# nucleo-shield.net
KiCad netlist of a schematic drawn in EAGLE
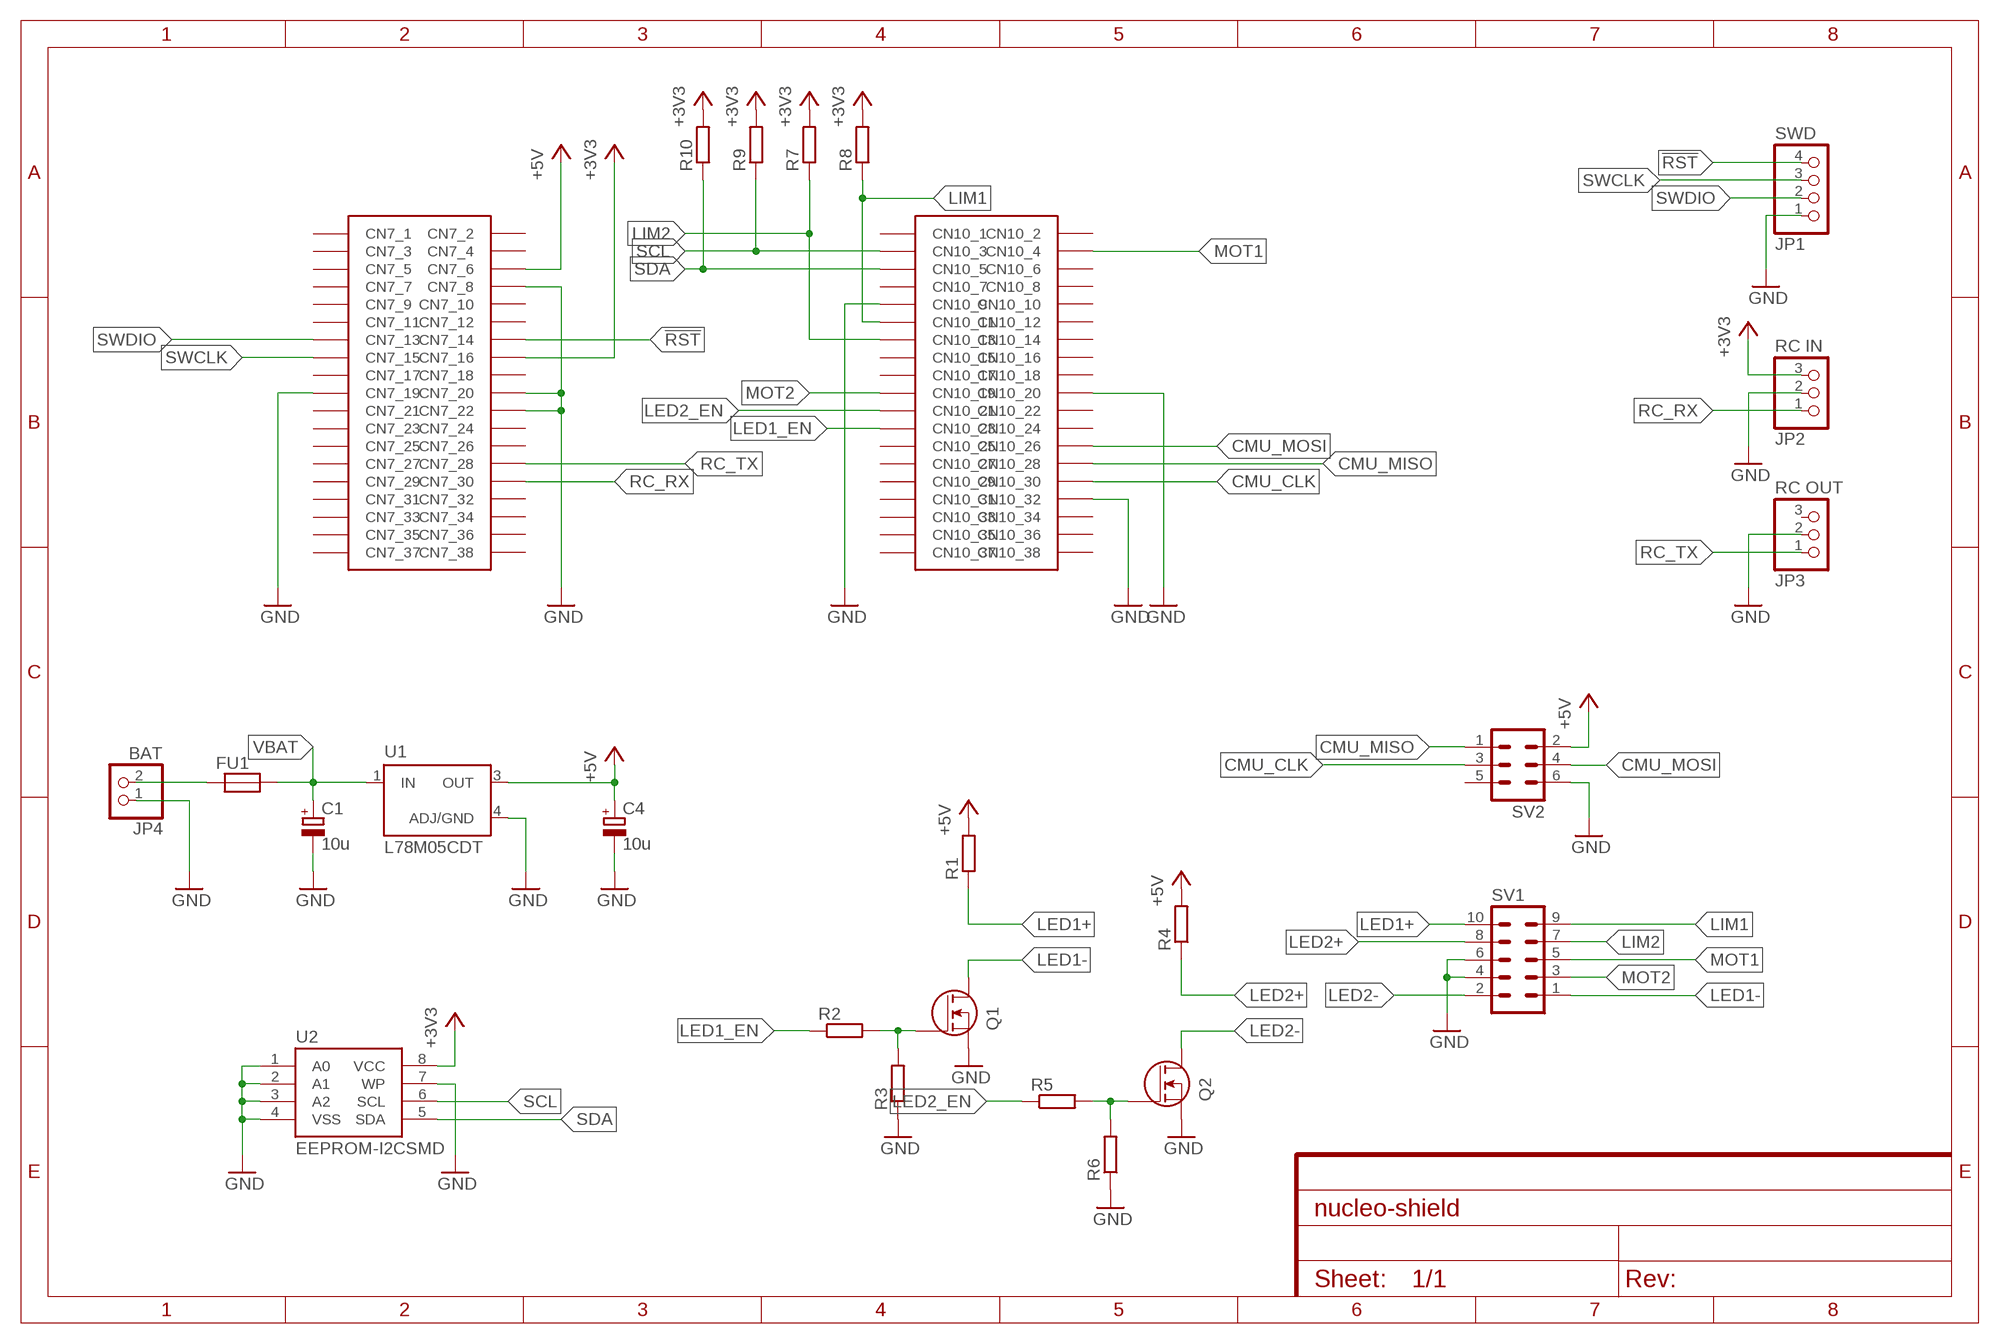
[diagram p0: schematic, sheet 1]

(export (version "E")
  (design (tool "Eeschema 10.0.6"))
  (components
    (comp (ref "C1")
      (value "10u")
      (footprint "eagle-import:SMC_A")
      (libsource (lib "eagle-import") (part "CPOL-EUSMCA"))
    )
    (comp (ref "C4")
      (value "10u")
      (footprint "eagle-import:SMC_A")
      (libsource (lib "eagle-import") (part "CPOL-EUSMCA"))
    )
    (comp (ref "FU1")
      (value "PTC_FUSE")
      (footprint "eagle-import:C1812K")
      (libsource (lib "eagle-import") (part "PTC_FUSE"))
    )
    (comp (ref "JP1")
      (value "SWD")
      (footprint "eagle-import:1X04")
      (libsource (lib "eagle-import") (part "PINHD-1X4"))
    )
    (comp (ref "JP2")
      (value "RC IN")
      (footprint "eagle-import:1X03")
      (libsource (lib "eagle-import") (part "PINHD-1X3"))
    )
    (comp (ref "JP3")
      (value "RC OUT")
      (footprint "eagle-import:1X03")
      (libsource (lib "eagle-import") (part "PINHD-1X3"))
    )
    (comp (ref "JP4")
      (value "BAT")
      (footprint "eagle-import:1X02")
      (libsource (lib "eagle-import") (part "PINHD-1X2"))
    )
    (comp (ref "Q1")
      (value "MOSFET-N-SOT23-3")
      (footprint "eagle-import:SOT23-3")
      (libsource (lib "eagle-import") (part "MOSFET-N-SOT23-3"))
    )
    (comp (ref "Q2")
      (value "MOSFET-N-SOT23-3")
      (footprint "eagle-import:SOT23-3")
      (libsource (lib "eagle-import") (part "MOSFET-N-SOT23-3"))
    )
    (comp (ref "R1")
      (value "R-EU_R0805")
      (footprint "eagle-import:R0805")
      (libsource (lib "eagle-import") (part "R-EU_R0805"))
    )
    (comp (ref "R2")
      (value "R-EU_R0805")
      (footprint "eagle-import:R0805")
      (libsource (lib "eagle-import") (part "R-EU_R0805"))
    )
    (comp (ref "R3")
      (value "R-EU_R0805")
      (footprint "eagle-import:R0805")
      (libsource (lib "eagle-import") (part "R-EU_R0805"))
    )
    (comp (ref "R4")
      (value "R-EU_R0805")
      (footprint "eagle-import:R0805")
      (libsource (lib "eagle-import") (part "R-EU_R0805"))
    )
    (comp (ref "R5")
      (value "R-EU_R0805")
      (footprint "eagle-import:R0805")
      (libsource (lib "eagle-import") (part "R-EU_R0805"))
    )
    (comp (ref "R6")
      (value "R-EU_R0805")
      (footprint "eagle-import:R0805")
      (libsource (lib "eagle-import") (part "R-EU_R0805"))
    )
    (comp (ref "R7")
      (value "R-EU_R0805")
      (footprint "eagle-import:R0805")
      (libsource (lib "eagle-import") (part "R-EU_R0805"))
    )
    (comp (ref "R8")
      (value "R-EU_R0805")
      (footprint "eagle-import:R0805")
      (libsource (lib "eagle-import") (part "R-EU_R0805"))
    )
    (comp (ref "R9")
      (value "R-EU_R0805")
      (footprint "eagle-import:R0805")
      (libsource (lib "eagle-import") (part "R-EU_R0805"))
    )
    (comp (ref "R10")
      (value "R-EU_R0805")
      (footprint "eagle-import:R0805")
      (libsource (lib "eagle-import") (part "R-EU_R0805"))
    )
    (comp (ref "SV1")
      (value "ML10L")
      (footprint "eagle-import:ML10L")
      (libsource (lib "eagle-import") (part "ML10L"))
    )
    (comp (ref "SV2")
      (value "ML6L")
      (footprint "eagle-import:ML6L")
      (libsource (lib "eagle-import") (part "ML6L"))
    )
    (comp (ref "U$2")
      (value "NUCLEO-MORPHO-64")
      (footprint "eagle-import:NUCLEO-64-MORPHO")
      (libsource (lib "eagle-import") (part "NUCLEO-MORPHO-64"))
    )
    (comp (ref "U1")
      (value "L78M05CDT")
      (footprint "eagle-import:DPAK")
      (libsource (lib "eagle-import") (part "VREG-3PIN-DPAK"))
    )
    (comp (ref "U2")
      (value "EEPROM-I2CSMD")
      (footprint "eagle-import:SO08")
      (libsource (lib "eagle-import") (part "EEPROM-I2CSMD"))
    )
  )
  (nets
    (net (code "1") (name "+3V3") (class "Default")
      (node (ref "JP2") (pin "3") (pinfunction "3_3") (pintype "passive"))
      (node (ref "R10") (pin "2") (pinfunction "2_2") (pintype "passive"))
      (node (ref "R7") (pin "2") (pinfunction "2_2") (pintype "passive"))
      (node (ref "R8") (pin "2") (pinfunction "2_2") (pintype "passive"))
      (node (ref "R9") (pin "2") (pinfunction "2_2") (pintype "passive"))
      (node (ref "U$2") (pin "CN7_16") (pinfunction "CN7_16_CN7_16") (pintype "bidirectional"))
      (node (ref "U2") (pin "8") (pinfunction "VCC_8") (pintype "power_in"))
    )
    (net (code "2") (name "+5V") (class "Default")
      (node (ref "C4") (pin "+") (pinfunction "+_+") (pintype "passive"))
      (node (ref "R1") (pin "2") (pinfunction "2_2") (pintype "passive"))
      (node (ref "R4") (pin "2") (pinfunction "2_2") (pintype "passive"))
      (node (ref "SV2") (pin "2") (pinfunction "2_2") (pintype "passive"))
      (node (ref "U$2") (pin "CN7_6") (pinfunction "CN7_6_CN7_6") (pintype "bidirectional"))
      (node (ref "U1") (pin "3") (pinfunction "OUT_3") (pintype "bidirectional"))
    )
    (net (code "3") (name "/~{RST}") (class "Default")
      (node (ref "JP1") (pin "4") (pinfunction "4_4") (pintype "passive"))
      (node (ref "U$2") (pin "CN7_14") (pinfunction "CN7_14_CN7_14") (pintype "bidirectional"))
    )
    (net (code "4") (name "CMU_CLK") (class "Default")
      (node (ref "SV2") (pin "3") (pinfunction "3_3") (pintype "passive"))
      (node (ref "U$2") (pin "CN10_30") (pinfunction "CN10_30_CN10_30") (pintype "bidirectional"))
    )
    (net (code "5") (name "CMU_MISO") (class "Default")
      (node (ref "SV2") (pin "1") (pinfunction "1_1") (pintype "passive"))
      (node (ref "U$2") (pin "CN10_28") (pinfunction "CN10_28_CN10_28") (pintype "bidirectional"))
    )
    (net (code "6") (name "CMU_MOSI") (class "Default")
      (node (ref "SV2") (pin "4") (pinfunction "4_4") (pintype "passive"))
      (node (ref "U$2") (pin "CN10_26") (pinfunction "CN10_26_CN10_26") (pintype "bidirectional"))
    )
    (net (code "7") (name "GND") (class "Default")
      (node (ref "C1") (pin "-") (pinfunction "-_-") (pintype "passive"))
      (node (ref "C4") (pin "-") (pinfunction "-_-") (pintype "passive"))
      (node (ref "JP1") (pin "1") (pinfunction "1_1") (pintype "passive"))
      (node (ref "JP2") (pin "2") (pinfunction "2_2") (pintype "passive"))
      (node (ref "JP3") (pin "2") (pinfunction "2_2") (pintype "passive"))
      (node (ref "JP4") (pin "1") (pinfunction "1_1") (pintype "passive"))
      (node (ref "Q1") (pin "2") (pinfunction "S_2") (pintype "passive"))
      (node (ref "Q2") (pin "2") (pinfunction "S_2") (pintype "passive"))
      (node (ref "R3") (pin "1") (pinfunction "1_1") (pintype "passive"))
      (node (ref "R6") (pin "1") (pinfunction "1_1") (pintype "passive"))
      (node (ref "SV1") (pin "4") (pinfunction "4_4") (pintype "passive"))
      (node (ref "SV1") (pin "6") (pinfunction "6_6") (pintype "passive"))
      (node (ref "SV2") (pin "6") (pinfunction "6_6") (pintype "passive"))
      (node (ref "U$2") (pin "CN10_20") (pinfunction "CN10_20_CN10_20") (pintype "bidirectional"))
      (node (ref "U$2") (pin "CN10_32") (pinfunction "CN10_32_CN10_32") (pintype "bidirectional"))
      (node (ref "U$2") (pin "CN10_9") (pinfunction "CN10_9_CN10_9") (pintype "bidirectional"))
      (node (ref "U$2") (pin "CN7_19") (pinfunction "CN7_19_CN7_19") (pintype "bidirectional"))
      (node (ref "U$2") (pin "CN7_20") (pinfunction "CN7_20_CN7_20") (pintype "bidirectional"))
      (node (ref "U$2") (pin "CN7_22") (pinfunction "CN7_22_CN7_22") (pintype "bidirectional"))
      (node (ref "U$2") (pin "CN7_8") (pinfunction "CN7_8_CN7_8") (pintype "bidirectional"))
      (node (ref "U1") (pin "4") (pinfunction "ADJ/GND_4") (pintype "bidirectional"))
      (node (ref "U2") (pin "1") (pinfunction "A0_1") (pintype "bidirectional"))
      (node (ref "U2") (pin "2") (pinfunction "A1_2") (pintype "bidirectional"))
      (node (ref "U2") (pin "3") (pinfunction "A2_3") (pintype "bidirectional"))
      (node (ref "U2") (pin "4") (pinfunction "VSS_4") (pintype "power_in"))
      (node (ref "U2") (pin "7") (pinfunction "WP_7") (pintype "bidirectional"))
    )
    (net (code "8") (name "LED1+") (class "Default")
      (node (ref "R1") (pin "1") (pinfunction "1_1") (pintype "passive"))
      (node (ref "SV1") (pin "10") (pinfunction "10_10") (pintype "passive"))
    )
    (net (code "9") (name "LED1-") (class "Default")
      (node (ref "Q1") (pin "3") (pinfunction "D_3") (pintype "passive"))
      (node (ref "SV1") (pin "1") (pinfunction "1_1") (pintype "passive"))
    )
    (net (code "10") (name "LED1_EN") (class "Default")
      (node (ref "R2") (pin "1") (pinfunction "1_1") (pintype "passive"))
      (node (ref "U$2") (pin "CN10_23") (pinfunction "CN10_23_CN10_23") (pintype "bidirectional"))
    )
    (net (code "11") (name "LED2+") (class "Default")
      (node (ref "R4") (pin "1") (pinfunction "1_1") (pintype "passive"))
      (node (ref "SV1") (pin "8") (pinfunction "8_8") (pintype "passive"))
    )
    (net (code "12") (name "LED2-") (class "Default")
      (node (ref "Q2") (pin "3") (pinfunction "D_3") (pintype "passive"))
      (node (ref "SV1") (pin "2") (pinfunction "2_2") (pintype "passive"))
    )
    (net (code "13") (name "LED2_EN") (class "Default")
      (node (ref "R5") (pin "1") (pinfunction "1_1") (pintype "passive"))
      (node (ref "U$2") (pin "CN10_21") (pinfunction "CN10_21_CN10_21") (pintype "bidirectional"))
    )
    (net (code "14") (name "LIM1") (class "Default")
      (node (ref "R8") (pin "1") (pinfunction "1_1") (pintype "passive"))
      (node (ref "SV1") (pin "9") (pinfunction "9_9") (pintype "passive"))
      (node (ref "U$2") (pin "CN10_11") (pinfunction "CN10_11_CN10_11") (pintype "bidirectional"))
    )
    (net (code "15") (name "LIM2") (class "Default")
      (node (ref "R7") (pin "1") (pinfunction "1_1") (pintype "passive"))
      (node (ref "SV1") (pin "7") (pinfunction "7_7") (pintype "passive"))
      (node (ref "U$2") (pin "CN10_13") (pinfunction "CN10_13_CN10_13") (pintype "bidirectional"))
    )
    (net (code "16") (name "MOT1") (class "Default")
      (node (ref "SV1") (pin "5") (pinfunction "5_5") (pintype "passive"))
      (node (ref "U$2") (pin "CN10_4") (pinfunction "CN10_4_CN10_4") (pintype "bidirectional"))
    )
    (net (code "17") (name "MOT2") (class "Default")
      (node (ref "SV1") (pin "3") (pinfunction "3_3") (pintype "passive"))
      (node (ref "U$2") (pin "CN10_19") (pinfunction "CN10_19_CN10_19") (pintype "bidirectional"))
    )
    (net (code "18") (name "Net-(FU1-Pad1)") (class "Default")
      (node (ref "FU1") (pin "1") (pinfunction "1_1") (pintype "passive"))
      (node (ref "JP4") (pin "2") (pinfunction "2_2") (pintype "passive"))
    )
    (net (code "19") (name "Net-(Q1-G)") (class "Default")
      (node (ref "Q1") (pin "1") (pinfunction "G_1") (pintype "passive"))
      (node (ref "R2") (pin "2") (pinfunction "2_2") (pintype "passive"))
      (node (ref "R3") (pin "2") (pinfunction "2_2") (pintype "passive"))
    )
    (net (code "20") (name "Net-(Q2-G)") (class "Default")
      (node (ref "Q2") (pin "1") (pinfunction "G_1") (pintype "passive"))
      (node (ref "R5") (pin "2") (pinfunction "2_2") (pintype "passive"))
      (node (ref "R6") (pin "2") (pinfunction "2_2") (pintype "passive"))
    )
    (net (code "21") (name "RC_RX") (class "Default")
      (node (ref "JP2") (pin "1") (pinfunction "1_1") (pintype "passive"))
      (node (ref "U$2") (pin "CN7_30") (pinfunction "CN7_30_CN7_30") (pintype "bidirectional"))
    )
    (net (code "22") (name "RC_TX") (class "Default")
      (node (ref "JP3") (pin "1") (pinfunction "1_1") (pintype "passive"))
      (node (ref "U$2") (pin "CN7_28") (pinfunction "CN7_28_CN7_28") (pintype "bidirectional"))
    )
    (net (code "23") (name "SCL") (class "Default")
      (node (ref "R9") (pin "1") (pinfunction "1_1") (pintype "passive"))
      (node (ref "U$2") (pin "CN10_3") (pinfunction "CN10_3_CN10_3") (pintype "bidirectional"))
      (node (ref "U2") (pin "6") (pinfunction "SCL_6") (pintype "bidirectional"))
    )
    (net (code "24") (name "SDA") (class "Default")
      (node (ref "R10") (pin "1") (pinfunction "1_1") (pintype "passive"))
      (node (ref "U$2") (pin "CN10_5") (pinfunction "CN10_5_CN10_5") (pintype "bidirectional"))
      (node (ref "U2") (pin "5") (pinfunction "SDA_5") (pintype "bidirectional"))
    )
    (net (code "25") (name "SWCLK") (class "Default")
      (node (ref "JP1") (pin "3") (pinfunction "3_3") (pintype "passive"))
      (node (ref "U$2") (pin "CN7_15") (pinfunction "CN7_15_CN7_15") (pintype "bidirectional"))
    )
    (net (code "26") (name "SWDIO") (class "Default")
      (node (ref "JP1") (pin "2") (pinfunction "2_2") (pintype "passive"))
      (node (ref "U$2") (pin "CN7_13") (pinfunction "CN7_13_CN7_13") (pintype "bidirectional"))
    )
    (net (code "27") (name "VBAT") (class "Default")
      (node (ref "C1") (pin "+") (pinfunction "+_+") (pintype "passive"))
      (node (ref "FU1") (pin "2") (pinfunction "2_2") (pintype "passive"))
      (node (ref "U1") (pin "1") (pinfunction "IN_1") (pintype "bidirectional"))
    )
    (net (code "28") (name "unconnected-(JP3-Pad3)") (class "Default")
      (node (ref "JP3") (pin "3") (pinfunction "3_3") (pintype "passive"))
    )
    (net (code "29") (name "unconnected-(SV2-Pad5)") (class "Default")
      (node (ref "SV2") (pin "5") (pinfunction "5_5") (pintype "passive"))
    )
    (net (code "30") (name "unconnected-(U$2-PadCN7_1)") (class "Default")
      (node (ref "U$2") (pin "CN7_1") (pinfunction "CN7_1_CN7_1") (pintype "bidirectional"))
    )
    (net (code "31") (name "unconnected-(U$2-PadCN7_2)") (class "Default")
      (node (ref "U$2") (pin "CN7_2") (pinfunction "CN7_2_CN7_2") (pintype "bidirectional"))
    )
    (net (code "32") (name "unconnected-(U$2-PadCN7_3)") (class "Default")
      (node (ref "U$2") (pin "CN7_3") (pinfunction "CN7_3_CN7_3") (pintype "bidirectional"))
    )
    (net (code "33") (name "unconnected-(U$2-PadCN7_4)") (class "Default")
      (node (ref "U$2") (pin "CN7_4") (pinfunction "CN7_4_CN7_4") (pintype "bidirectional"))
    )
    (net (code "34") (name "unconnected-(U$2-PadCN7_5)") (class "Default")
      (node (ref "U$2") (pin "CN7_5") (pinfunction "CN7_5_CN7_5") (pintype "bidirectional"))
    )
    (net (code "35") (name "unconnected-(U$2-PadCN7_7)") (class "Default")
      (node (ref "U$2") (pin "CN7_7") (pinfunction "CN7_7_CN7_7") (pintype "bidirectional"))
    )
    (net (code "36") (name "unconnected-(U$2-PadCN7_9)") (class "Default")
      (node (ref "U$2") (pin "CN7_9") (pinfunction "CN7_9_CN7_9") (pintype "bidirectional"))
    )
    (net (code "37") (name "unconnected-(U$2-PadCN7_10)") (class "Default")
      (node (ref "U$2") (pin "CN7_10") (pinfunction "CN7_10_CN7_10") (pintype "bidirectional"))
    )
    (net (code "38") (name "unconnected-(U$2-PadCN7_11)") (class "Default")
      (node (ref "U$2") (pin "CN7_11") (pinfunction "CN7_11_CN7_11") (pintype "bidirectional"))
    )
    (net (code "39") (name "unconnected-(U$2-PadCN7_12)") (class "Default")
      (node (ref "U$2") (pin "CN7_12") (pinfunction "CN7_12_CN7_12") (pintype "bidirectional"))
    )
    (net (code "40") (name "unconnected-(U$2-PadCN7_17)") (class "Default")
      (node (ref "U$2") (pin "CN7_17") (pinfunction "CN7_17_CN7_17") (pintype "bidirectional"))
    )
    (net (code "41") (name "unconnected-(U$2-PadCN7_18)") (class "Default")
      (node (ref "U$2") (pin "CN7_18") (pinfunction "CN7_18_CN7_18") (pintype "bidirectional"))
    )
    (net (code "42") (name "unconnected-(U$2-PadCN7_21)") (class "Default")
      (node (ref "U$2") (pin "CN7_21") (pinfunction "CN7_21_CN7_21") (pintype "bidirectional"))
    )
    (net (code "43") (name "unconnected-(U$2-PadCN7_23)") (class "Default")
      (node (ref "U$2") (pin "CN7_23") (pinfunction "CN7_23_CN7_23") (pintype "bidirectional"))
    )
    (net (code "44") (name "unconnected-(U$2-PadCN7_24)") (class "Default")
      (node (ref "U$2") (pin "CN7_24") (pinfunction "CN7_24_CN7_24") (pintype "bidirectional"))
    )
    (net (code "45") (name "unconnected-(U$2-PadCN7_25)") (class "Default")
      (node (ref "U$2") (pin "CN7_25") (pinfunction "CN7_25_CN7_25") (pintype "bidirectional"))
    )
    (net (code "46") (name "unconnected-(U$2-PadCN7_26)") (class "Default")
      (node (ref "U$2") (pin "CN7_26") (pinfunction "CN7_26_CN7_26") (pintype "bidirectional"))
    )
    (net (code "47") (name "unconnected-(U$2-PadCN7_27)") (class "Default")
      (node (ref "U$2") (pin "CN7_27") (pinfunction "CN7_27_CN7_27") (pintype "bidirectional"))
    )
    (net (code "48") (name "unconnected-(U$2-PadCN7_29)") (class "Default")
      (node (ref "U$2") (pin "CN7_29") (pinfunction "CN7_29_CN7_29") (pintype "bidirectional"))
    )
    (net (code "49") (name "unconnected-(U$2-PadCN7_31)") (class "Default")
      (node (ref "U$2") (pin "CN7_31") (pinfunction "CN7_31_CN7_31") (pintype "bidirectional"))
    )
    (net (code "50") (name "unconnected-(U$2-PadCN7_32)") (class "Default")
      (node (ref "U$2") (pin "CN7_32") (pinfunction "CN7_32_CN7_32") (pintype "bidirectional"))
    )
    (net (code "51") (name "unconnected-(U$2-PadCN7_33)") (class "Default")
      (node (ref "U$2") (pin "CN7_33") (pinfunction "CN7_33_CN7_33") (pintype "bidirectional"))
    )
    (net (code "52") (name "unconnected-(U$2-PadCN7_34)") (class "Default")
      (node (ref "U$2") (pin "CN7_34") (pinfunction "CN7_34_CN7_34") (pintype "bidirectional"))
    )
    (net (code "53") (name "unconnected-(U$2-PadCN7_35)") (class "Default")
      (node (ref "U$2") (pin "CN7_35") (pinfunction "CN7_35_CN7_35") (pintype "bidirectional"))
    )
    (net (code "54") (name "unconnected-(U$2-PadCN7_36)") (class "Default")
      (node (ref "U$2") (pin "CN7_36") (pinfunction "CN7_36_CN7_36") (pintype "bidirectional"))
    )
    (net (code "55") (name "unconnected-(U$2-PadCN7_37)") (class "Default")
      (node (ref "U$2") (pin "CN7_37") (pinfunction "CN7_37_CN7_37") (pintype "bidirectional"))
    )
    (net (code "56") (name "unconnected-(U$2-PadCN7_38)") (class "Default")
      (node (ref "U$2") (pin "CN7_38") (pinfunction "CN7_38_CN7_38") (pintype "bidirectional"))
    )
    (net (code "57") (name "unconnected-(U$2-PadCN10_1)") (class "Default")
      (node (ref "U$2") (pin "CN10_1") (pinfunction "CN10_1_CN10_1") (pintype "bidirectional"))
    )
    (net (code "58") (name "unconnected-(U$2-PadCN10_2)") (class "Default")
      (node (ref "U$2") (pin "CN10_2") (pinfunction "CN10_2_CN10_2") (pintype "bidirectional"))
    )
    (net (code "59") (name "unconnected-(U$2-PadCN10_6)") (class "Default")
      (node (ref "U$2") (pin "CN10_6") (pinfunction "CN10_6_CN10_6") (pintype "bidirectional"))
    )
    (net (code "60") (name "unconnected-(U$2-PadCN10_7)") (class "Default")
      (node (ref "U$2") (pin "CN10_7") (pinfunction "CN10_7_CN10_7") (pintype "bidirectional"))
    )
    (net (code "61") (name "unconnected-(U$2-PadCN10_8)") (class "Default")
      (node (ref "U$2") (pin "CN10_8") (pinfunction "CN10_8_CN10_8") (pintype "bidirectional"))
    )
    (net (code "62") (name "unconnected-(U$2-PadCN10_10)") (class "Default")
      (node (ref "U$2") (pin "CN10_10") (pinfunction "CN10_10_CN10_10") (pintype "bidirectional"))
    )
    (net (code "63") (name "unconnected-(U$2-PadCN10_12)") (class "Default")
      (node (ref "U$2") (pin "CN10_12") (pinfunction "CN10_12_CN10_12") (pintype "bidirectional"))
    )
    (net (code "64") (name "unconnected-(U$2-PadCN10_14)") (class "Default")
      (node (ref "U$2") (pin "CN10_14") (pinfunction "CN10_14_CN10_14") (pintype "bidirectional"))
    )
    (net (code "65") (name "unconnected-(U$2-PadCN10_15)") (class "Default")
      (node (ref "U$2") (pin "CN10_15") (pinfunction "CN10_15_CN10_15") (pintype "bidirectional"))
    )
    (net (code "66") (name "unconnected-(U$2-PadCN10_16)") (class "Default")
      (node (ref "U$2") (pin "CN10_16") (pinfunction "CN10_16_CN10_16") (pintype "bidirectional"))
    )
    (net (code "67") (name "unconnected-(U$2-PadCN10_17)") (class "Default")
      (node (ref "U$2") (pin "CN10_17") (pinfunction "CN10_17_CN10_17") (pintype "bidirectional"))
    )
    (net (code "68") (name "unconnected-(U$2-PadCN10_18)") (class "Default")
      (node (ref "U$2") (pin "CN10_18") (pinfunction "CN10_18_CN10_18") (pintype "bidirectional"))
    )
    (net (code "69") (name "unconnected-(U$2-PadCN10_22)") (class "Default")
      (node (ref "U$2") (pin "CN10_22") (pinfunction "CN10_22_CN10_22") (pintype "bidirectional"))
    )
    (net (code "70") (name "unconnected-(U$2-PadCN10_24)") (class "Default")
      (node (ref "U$2") (pin "CN10_24") (pinfunction "CN10_24_CN10_24") (pintype "bidirectional"))
    )
    (net (code "71") (name "unconnected-(U$2-PadCN10_25)") (class "Default")
      (node (ref "U$2") (pin "CN10_25") (pinfunction "CN10_25_CN10_25") (pintype "bidirectional"))
    )
    (net (code "72") (name "unconnected-(U$2-PadCN10_27)") (class "Default")
      (node (ref "U$2") (pin "CN10_27") (pinfunction "CN10_27_CN10_27") (pintype "bidirectional"))
    )
    (net (code "73") (name "unconnected-(U$2-PadCN10_29)") (class "Default")
      (node (ref "U$2") (pin "CN10_29") (pinfunction "CN10_29_CN10_29") (pintype "bidirectional"))
    )
    (net (code "74") (name "unconnected-(U$2-PadCN10_31)") (class "Default")
      (node (ref "U$2") (pin "CN10_31") (pinfunction "CN10_31_CN10_31") (pintype "bidirectional"))
    )
    (net (code "75") (name "unconnected-(U$2-PadCN10_33)") (class "Default")
      (node (ref "U$2") (pin "CN10_33") (pinfunction "CN10_33_CN10_33") (pintype "bidirectional"))
    )
    (net (code "76") (name "unconnected-(U$2-PadCN10_34)") (class "Default")
      (node (ref "U$2") (pin "CN10_34") (pinfunction "CN10_34_CN10_34") (pintype "bidirectional"))
    )
    (net (code "77") (name "unconnected-(U$2-PadCN10_35)") (class "Default")
      (node (ref "U$2") (pin "CN10_35") (pinfunction "CN10_35_CN10_35") (pintype "bidirectional"))
    )
    (net (code "78") (name "unconnected-(U$2-PadCN10_36)") (class "Default")
      (node (ref "U$2") (pin "CN10_36") (pinfunction "CN10_36_CN10_36") (pintype "bidirectional"))
    )
    (net (code "79") (name "unconnected-(U$2-PadCN10_37)") (class "Default")
      (node (ref "U$2") (pin "CN10_37") (pinfunction "CN10_37_CN10_37") (pintype "bidirectional"))
    )
    (net (code "80") (name "unconnected-(U$2-PadCN10_38)") (class "Default")
      (node (ref "U$2") (pin "CN10_38") (pinfunction "CN10_38_CN10_38") (pintype "bidirectional"))
    )
  )
)
